# mcc.net
KiCad netlist of a schematic drawn in EAGLE
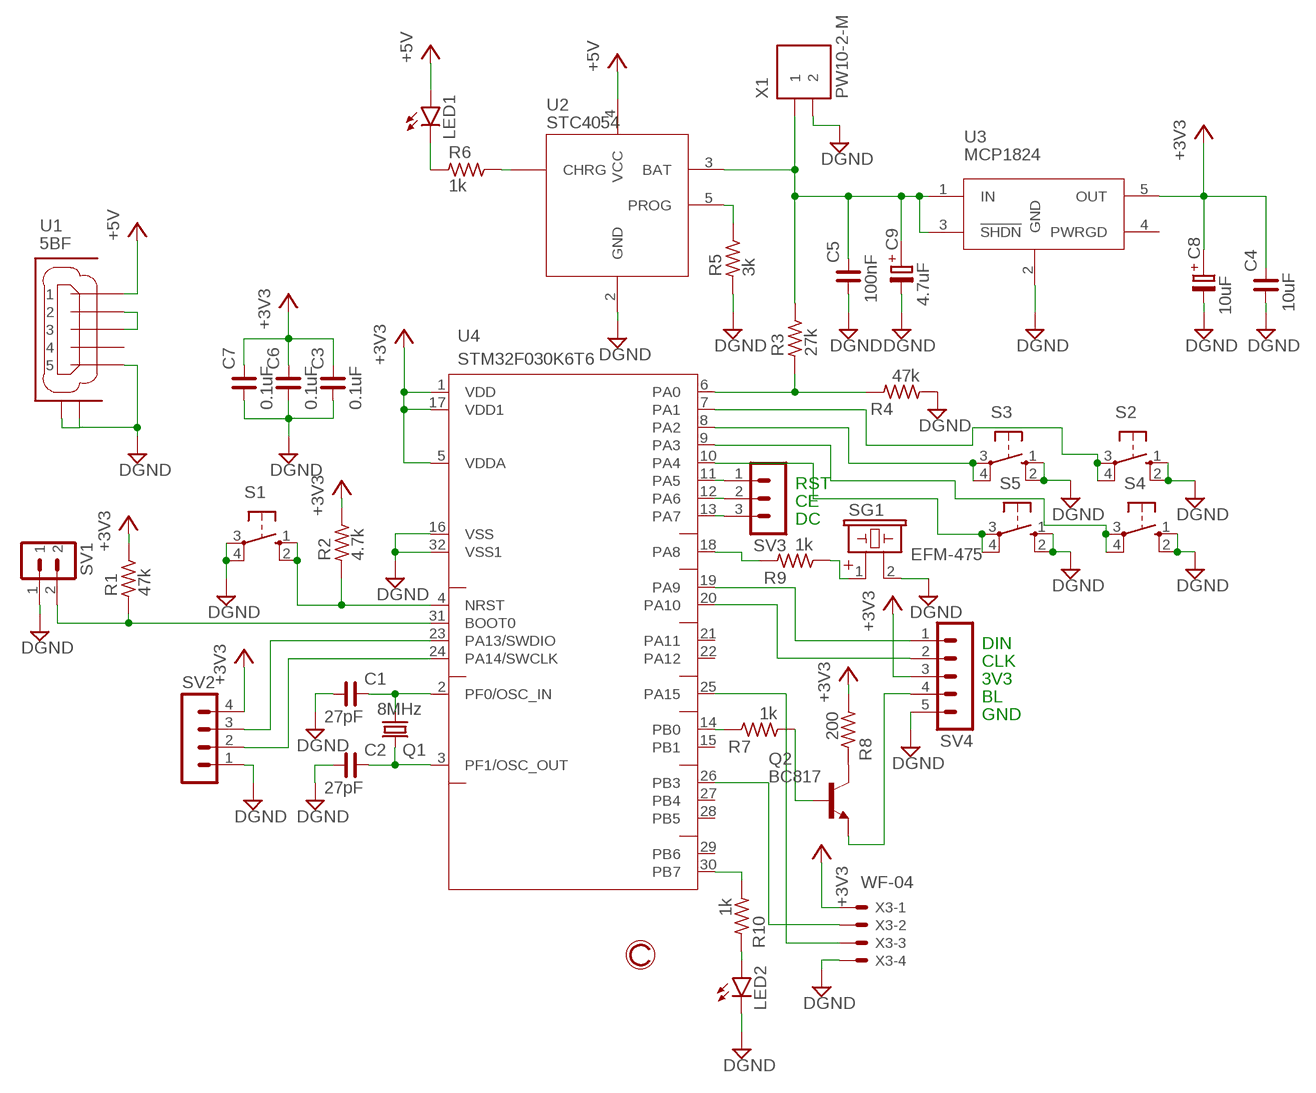
[diagram p0: schematic, sheet 1]

(export (version "E")
  (design (tool "Eeschema 10.0.6"))
  (components
    (comp (ref "C1")
      (value "27pF")
      (footprint "eagle-import:C0805")
      (libsource (lib "eagle-import") (part "C_0805"))
    )
    (comp (ref "C2")
      (value "27pF")
      (footprint "eagle-import:C0805")
      (libsource (lib "eagle-import") (part "C_0805"))
    )
    (comp (ref "C3")
      (value "0.1uF")
      (footprint "eagle-import:C0805")
      (libsource (lib "eagle-import") (part "C_0805"))
    )
    (comp (ref "C4")
      (value "10uF")
      (footprint "eagle-import:C1206")
      (libsource (lib "eagle-import") (part "C_1206"))
    )
    (comp (ref "C5")
      (value "100nF")
      (footprint "eagle-import:C0805")
      (libsource (lib "eagle-import") (part "C_0805"))
    )
    (comp (ref "C6")
      (value "0.1uF")
      (footprint "eagle-import:C0805")
      (libsource (lib "eagle-import") (part "C_0805"))
    )
    (comp (ref "C7")
      (value "0.1uF")
      (footprint "eagle-import:C0805")
      (libsource (lib "eagle-import") (part "C_0805"))
    )
    (comp (ref "C8")
      (value "10uF")
      (footprint "eagle-import:SV-C")
      (libsource (lib "eagle-import") (part "C-PR-SMD-SV-C"))
    )
    (comp (ref "C9")
      (value "4.7uF")
      (footprint "eagle-import:SV-C")
      (libsource (lib "eagle-import") (part "C-PR-SMD-SV-C"))
    )
    (comp (ref "LED1")
      (value "LEDSML0805")
      (footprint "eagle-import:SML0805")
      (libsource (lib "eagle-import") (part "LEDSML0805"))
    )
    (comp (ref "LED2")
      (value "LEDSML0805")
      (footprint "eagle-import:SML0805")
      (libsource (lib "eagle-import") (part "LEDSML0805"))
    )
    (comp (ref "Q1")
      (value "8MHz")
      (footprint "eagle-import:HC49UP")
      (libsource (lib "eagle-import") (part "CRYSTALHC49UP"))
    )
    (comp (ref "Q2")
      (value "BC817")
      (footprint "eagle-import:SOT23-BEC")
      (libsource (lib "eagle-import") (part "BC817SMD-40"))
    )
    (comp (ref "R1")
      (value "47k")
      (footprint "eagle-import:R0805")
      (libsource (lib "eagle-import") (part "R_0805"))
    )
    (comp (ref "R2")
      (value "4.7k")
      (footprint "eagle-import:R0805")
      (libsource (lib "eagle-import") (part "R_0805"))
    )
    (comp (ref "R3")
      (value "27k")
      (footprint "eagle-import:R0805")
      (libsource (lib "eagle-import") (part "R_0805"))
    )
    (comp (ref "R4")
      (value "47k")
      (footprint "eagle-import:R0805")
      (libsource (lib "eagle-import") (part "R_0805"))
    )
    (comp (ref "R5")
      (value "3k")
      (footprint "eagle-import:R0805")
      (libsource (lib "eagle-import") (part "R_0805"))
    )
    (comp (ref "R6")
      (value "1k")
      (footprint "eagle-import:R0805")
      (libsource (lib "eagle-import") (part "R_0805"))
    )
    (comp (ref "R7")
      (value "1k")
      (footprint "eagle-import:R0805")
      (libsource (lib "eagle-import") (part "R_0805"))
    )
    (comp (ref "R8")
      (value "200")
      (footprint "eagle-import:R0805")
      (libsource (lib "eagle-import") (part "R_0805"))
    )
    (comp (ref "R9")
      (value "1k")
      (footprint "eagle-import:R0805")
      (libsource (lib "eagle-import") (part "R_0805"))
    )
    (comp (ref "R10")
      (value "1k")
      (footprint "eagle-import:R0805")
      (libsource (lib "eagle-import") (part "R_0805"))
    )
    (comp (ref "S1")
      (value "10-XX")
      (footprint "eagle-import:B3F-10XX")
      (fields (field (name "MPN") "B3F-1000"))
      (libsource (lib "eagle-import") (part "10-XX"))
    )
    (comp (ref "S2")
      (value "10-XX")
      (footprint "eagle-import:B3F-10XX")
      (fields (field (name "MPN") "B3F-1000"))
      (libsource (lib "eagle-import") (part "10-XX"))
    )
    (comp (ref "S3")
      (value "10-XX")
      (footprint "eagle-import:B3F-10XX")
      (fields (field (name "MPN") "B3F-1000"))
      (libsource (lib "eagle-import") (part "10-XX"))
    )
    (comp (ref "S4")
      (value "10-XX")
      (footprint "eagle-import:B3F-10XX")
      (fields (field (name "MPN") "B3F-1000"))
      (libsource (lib "eagle-import") (part "10-XX"))
    )
    (comp (ref "S5")
      (value "10-XX")
      (footprint "eagle-import:B3F-10XX")
      (fields (field (name "MPN") "B3F-1000"))
      (libsource (lib "eagle-import") (part "10-XX"))
    )
    (comp (ref "SG1")
      (value "EFM-475")
      (footprint "eagle-import:EFM-472")
      (libsource (lib "eagle-import") (part "EFM-475"))
    )
    (comp (ref "SV1")
      (value "MA02-1")
      (footprint "eagle-import:MA02-1")
      (libsource (lib "eagle-import") (part "MA02-1"))
    )
    (comp (ref "SV2")
      (value "MA04-1")
      (footprint "eagle-import:MA04-1")
      (libsource (lib "eagle-import") (part "MA04-1"))
    )
    (comp (ref "SV3")
      (value "MA03-1")
      (footprint "eagle-import:MA03-1")
      (libsource (lib "eagle-import") (part "MA03-1"))
    )
    (comp (ref "SV4")
      (value "MA05-1")
      (footprint "eagle-import:MA05-1")
      (libsource (lib "eagle-import") (part "MA05-1"))
    )
    (comp (ref "U1")
      (value "5BF")
      (footprint "eagle-import:MICRO-USB-5BF")
      (libsource (lib "eagle-import") (part "MICRO-USB-5BF"))
    )
    (comp (ref "U2")
      (value "STC4054")
      (footprint "eagle-import:SOT23-5L")
      (libsource (lib "eagle-import") (part "STC4054"))
    )
    (comp (ref "U3")
      (value "MCP1824")
      (footprint "eagle-import:SOT23-5L")
      (libsource (lib "eagle-import") (part "MCP1824"))
    )
    (comp (ref "U4")
      (value "STM32F030K6T6")
      (footprint "eagle-import:LQFP-32")
      (libsource (lib "eagle-import") (part "STM32F030K6T6"))
    )
    (comp (ref "X1")
      (value "PW10-2-M")
      (footprint "eagle-import:MKS1852-6-0-202")
      (libsource (lib "eagle-import") (part "MKS1852-6-0-202"))
    )
    (comp (ref "X3")
      (value "WF-04")
      (footprint "eagle-import:22-23-2041")
      (fields (field (name "MF") "MOLEX") (field (name "MPN") "22-23-2041"))
      (libsource (lib "eagle-import") (part "22-23-2041"))
    )
  )
  (nets
    (net (code "1") (name "+3V3") (class "Default")
      (node (ref "C3") (pin "2") (pinfunction "2_2") (pintype "passive"))
      (node (ref "C4") (pin "2") (pinfunction "2_2") (pintype "passive"))
      (node (ref "C6") (pin "2") (pinfunction "2_2") (pintype "passive"))
      (node (ref "C7") (pin "2") (pinfunction "2_2") (pintype "passive"))
      (node (ref "C8") (pin "+") (pinfunction "+_+") (pintype "passive"))
      (node (ref "R1") (pin "2") (pinfunction "2_2") (pintype "passive"))
      (node (ref "R2") (pin "2") (pinfunction "2_2") (pintype "passive"))
      (node (ref "R8") (pin "1") (pinfunction "1_1") (pintype "passive"))
      (node (ref "SV2") (pin "4") (pinfunction "4_4") (pintype "passive"))
      (node (ref "SV4") (pin "3") (pinfunction "3_3") (pintype "passive"))
      (node (ref "U3") (pin "5") (pinfunction "OUT_5") (pintype "bidirectional"))
      (node (ref "U4") (pin "1") (pinfunction "VDD_1") (pintype "bidirectional"))
      (node (ref "U4") (pin "17") (pinfunction "VDD1_17") (pintype "bidirectional"))
      (node (ref "U4") (pin "5") (pinfunction "VDDA_5") (pintype "bidirectional"))
      (node (ref "X3") (pin "1") (pinfunction "S_1") (pintype "passive"))
    )
    (net (code "2") (name "+5V") (class "Default")
      (node (ref "LED1") (pin "A") (pinfunction "A_A") (pintype "passive"))
      (node (ref "U1") (pin "1") (pinfunction "1_1") (pintype "input"))
      (node (ref "U2") (pin "4") (pinfunction "VCC_4") (pintype "bidirectional"))
    )
    (net (code "3") (name "DGND") (class "Default")
      (node (ref "C1") (pin "1") (pinfunction "1_1") (pintype "passive"))
      (node (ref "C2") (pin "1") (pinfunction "1_1") (pintype "passive"))
      (node (ref "C3") (pin "1") (pinfunction "1_1") (pintype "passive"))
      (node (ref "C4") (pin "1") (pinfunction "1_1") (pintype "passive"))
      (node (ref "C5") (pin "1") (pinfunction "1_1") (pintype "passive"))
      (node (ref "C6") (pin "1") (pinfunction "1_1") (pintype "passive"))
      (node (ref "C7") (pin "1") (pinfunction "1_1") (pintype "passive"))
      (node (ref "C8") (pin "-") (pinfunction "-_-") (pintype "passive"))
      (node (ref "C9") (pin "-") (pinfunction "-_-") (pintype "passive"))
      (node (ref "LED2") (pin "C") (pinfunction "C_C") (pintype "passive"))
      (node (ref "R4") (pin "1") (pinfunction "1_1") (pintype "passive"))
      (node (ref "R5") (pin "1") (pinfunction "1_1") (pintype "passive"))
      (node (ref "S1") (pin "3") (pinfunction "P_3") (pintype "passive"))
      (node (ref "S1") (pin "4") (pinfunction "P1_4") (pintype "passive"))
      (node (ref "S2") (pin "1") (pinfunction "S_1") (pintype "passive"))
      (node (ref "S2") (pin "2") (pinfunction "S1_2") (pintype "passive"))
      (node (ref "S3") (pin "1") (pinfunction "S_1") (pintype "passive"))
      (node (ref "S3") (pin "2") (pinfunction "S1_2") (pintype "passive"))
      (node (ref "S4") (pin "1") (pinfunction "S_1") (pintype "passive"))
      (node (ref "S4") (pin "2") (pinfunction "S1_2") (pintype "passive"))
      (node (ref "S5") (pin "1") (pinfunction "S_1") (pintype "passive"))
      (node (ref "S5") (pin "2") (pinfunction "S1_2") (pintype "passive"))
      (node (ref "SG1") (pin "2") (pinfunction "2_2") (pintype "passive"))
      (node (ref "SV1") (pin "1") (pinfunction "1_1") (pintype "passive"))
      (node (ref "SV2") (pin "1") (pinfunction "1_1") (pintype "passive"))
      (node (ref "SV4") (pin "5") (pinfunction "5_5") (pintype "passive"))
      (node (ref "U1") (pin "5") (pinfunction "5_5") (pintype "input"))
      (node (ref "U1") (pin "GND1") (pinfunction "GND1_GND1") (pintype "bidirectional"))
      (node (ref "U1") (pin "GND2") (pinfunction "GND2_GND2") (pintype "bidirectional"))
      (node (ref "U2") (pin "2") (pinfunction "GND_2") (pintype "bidirectional"))
      (node (ref "U3") (pin "2") (pinfunction "GND_2") (pintype "bidirectional"))
      (node (ref "U4") (pin "16") (pinfunction "VSS_16") (pintype "bidirectional"))
      (node (ref "U4") (pin "32") (pinfunction "VSS1_32") (pintype "bidirectional"))
      (node (ref "X1") (pin "2") (pinfunction "2_2") (pintype "input"))
      (node (ref "X3") (pin "4") (pinfunction "S_4") (pintype "passive"))
    )
    (net (code "4") (name "Net-(LED1-PadC)") (class "Default")
      (node (ref "LED1") (pin "C") (pinfunction "C_C") (pintype "passive"))
      (node (ref "R6") (pin "1") (pinfunction "1_1") (pintype "passive"))
    )
    (net (code "5") (name "Net-(LED2-PadA)") (class "Default")
      (node (ref "LED2") (pin "A") (pinfunction "A_A") (pintype "passive"))
      (node (ref "R10") (pin "2") (pinfunction "2_2") (pintype "passive"))
    )
    (net (code "6") (name "Net-(Q2-PadB)") (class "Default")
      (node (ref "Q2") (pin "B") (pinfunction "B_B") (pintype "passive"))
      (node (ref "R7") (pin "1") (pinfunction "1_1") (pintype "passive"))
    )
    (net (code "7") (name "Net-(Q2-PadC)") (class "Default")
      (node (ref "Q2") (pin "C") (pinfunction "C_C") (pintype "passive"))
      (node (ref "R8") (pin "2") (pinfunction "2_2") (pintype "passive"))
    )
    (net (code "8") (name "Net-(Q2-PadE)") (class "Default")
      (node (ref "Q2") (pin "E") (pinfunction "E_E") (pintype "passive"))
      (node (ref "SV4") (pin "4") (pinfunction "4_4") (pintype "passive"))
    )
    (net (code "9") (name "Net-(R9-Pad1)") (class "Default")
      (node (ref "R9") (pin "1") (pinfunction "1_1") (pintype "passive"))
      (node (ref "SG1") (pin "1") (pinfunction "1_1") (pintype "passive"))
    )
    (net (code "10") (name "Net-(S1-S)") (class "Default")
      (node (ref "R2") (pin "1") (pinfunction "1_1") (pintype "passive"))
      (node (ref "S1") (pin "1") (pinfunction "S_1") (pintype "passive"))
      (node (ref "S1") (pin "2") (pinfunction "S1_2") (pintype "passive"))
      (node (ref "U4") (pin "4") (pinfunction "NRST_4") (pintype "bidirectional"))
    )
    (net (code "11") (name "Net-(S2-P)") (class "Default")
      (node (ref "S2") (pin "3") (pinfunction "P_3") (pintype "passive"))
      (node (ref "S2") (pin "4") (pinfunction "P1_4") (pintype "passive"))
      (node (ref "U4") (pin "7") (pinfunction "PA1_7") (pintype "bidirectional"))
    )
    (net (code "12") (name "Net-(S3-P)") (class "Default")
      (node (ref "S3") (pin "3") (pinfunction "P_3") (pintype "passive"))
      (node (ref "S3") (pin "4") (pinfunction "P1_4") (pintype "passive"))
      (node (ref "U4") (pin "8") (pinfunction "PA2_8") (pintype "bidirectional"))
    )
    (net (code "13") (name "Net-(S4-P)") (class "Default")
      (node (ref "S4") (pin "3") (pinfunction "P_3") (pintype "passive"))
      (node (ref "S4") (pin "4") (pinfunction "P1_4") (pintype "passive"))
      (node (ref "U4") (pin "9") (pinfunction "PA3_9") (pintype "bidirectional"))
    )
    (net (code "14") (name "Net-(S5-P)") (class "Default")
      (node (ref "S5") (pin "3") (pinfunction "P_3") (pintype "passive"))
      (node (ref "S5") (pin "4") (pinfunction "P1_4") (pintype "passive"))
      (node (ref "U4") (pin "10") (pinfunction "PA4_10") (pintype "bidirectional"))
    )
    (net (code "15") (name "Net-(U1-Pad2)") (class "Default")
      (node (ref "U1") (pin "2") (pinfunction "2_2") (pintype "input"))
      (node (ref "U1") (pin "3") (pinfunction "3_3") (pintype "input"))
    )
    (net (code "16") (name "Net-(U2-BAT)") (class "Default")
      (node (ref "C5") (pin "2") (pinfunction "2_2") (pintype "passive"))
      (node (ref "C9") (pin "+") (pinfunction "+_+") (pintype "passive"))
      (node (ref "R3") (pin "2") (pinfunction "2_2") (pintype "passive"))
      (node (ref "U2") (pin "3") (pinfunction "BAT_3") (pintype "bidirectional"))
      (node (ref "U3") (pin "1") (pinfunction "IN_1") (pintype "bidirectional"))
      (node (ref "U3") (pin "3") (pinfunction "~{SHDN}_3") (pintype "bidirectional"))
      (node (ref "X1") (pin "1") (pinfunction "1_1") (pintype "input"))
    )
    (net (code "17") (name "Net-(U2-CHRG)") (class "Default")
      (node (ref "R6") (pin "2") (pinfunction "2_2") (pintype "passive"))
      (node (ref "U2") (pin "1") (pinfunction "CHRG_1") (pintype "bidirectional"))
    )
    (net (code "18") (name "Net-(U2-PROG)") (class "Default")
      (node (ref "R5") (pin "2") (pinfunction "2_2") (pintype "passive"))
      (node (ref "U2") (pin "5") (pinfunction "PROG_5") (pintype "bidirectional"))
    )
    (net (code "19") (name "Net-(U4-BOOT0)") (class "Default")
      (node (ref "R1") (pin "1") (pinfunction "1_1") (pintype "passive"))
      (node (ref "SV1") (pin "2") (pinfunction "2_2") (pintype "passive"))
      (node (ref "U4") (pin "31") (pinfunction "BOOT0_31") (pintype "bidirectional"))
    )
    (net (code "20") (name "Net-(U4-PA0)") (class "Default")
      (node (ref "R3") (pin "1") (pinfunction "1_1") (pintype "passive"))
      (node (ref "R4") (pin "2") (pinfunction "2_2") (pintype "passive"))
      (node (ref "U4") (pin "6") (pinfunction "PA0_6") (pintype "bidirectional"))
    )
    (net (code "21") (name "Net-(U4-PA5)") (class "Default")
      (node (ref "SV3") (pin "1") (pinfunction "1_1") (pintype "passive"))
      (node (ref "U4") (pin "11") (pinfunction "PA5_11") (pintype "bidirectional"))
    )
    (net (code "22") (name "Net-(U4-PA6)") (class "Default")
      (node (ref "SV3") (pin "2") (pinfunction "2_2") (pintype "passive"))
      (node (ref "U4") (pin "12") (pinfunction "PA6_12") (pintype "bidirectional"))
    )
    (net (code "23") (name "Net-(U4-PA7)") (class "Default")
      (node (ref "SV3") (pin "3") (pinfunction "3_3") (pintype "passive"))
      (node (ref "U4") (pin "13") (pinfunction "PA7_13") (pintype "bidirectional"))
    )
    (net (code "24") (name "Net-(U4-PA8)") (class "Default")
      (node (ref "R9") (pin "2") (pinfunction "2_2") (pintype "passive"))
      (node (ref "U4") (pin "18") (pinfunction "PA8_18") (pintype "bidirectional"))
    )
    (net (code "25") (name "Net-(U4-PA9)") (class "Default")
      (node (ref "SV4") (pin "1") (pinfunction "1_1") (pintype "passive"))
      (node (ref "U4") (pin "19") (pinfunction "PA9_19") (pintype "bidirectional"))
    )
    (net (code "26") (name "Net-(U4-PA10)") (class "Default")
      (node (ref "SV4") (pin "2") (pinfunction "2_2") (pintype "passive"))
      (node (ref "U4") (pin "20") (pinfunction "PA10_20") (pintype "bidirectional"))
    )
    (net (code "27") (name "Net-(U4-PA13{slash}SWDIO)") (class "Default")
      (node (ref "SV2") (pin "3") (pinfunction "3_3") (pintype "passive"))
      (node (ref "U4") (pin "23") (pinfunction "PA13/SWDIO_23") (pintype "bidirectional"))
    )
    (net (code "28") (name "Net-(U4-PA14{slash}SWCLK)") (class "Default")
      (node (ref "SV2") (pin "2") (pinfunction "2_2") (pintype "passive"))
      (node (ref "U4") (pin "24") (pinfunction "PA14/SWCLK_24") (pintype "bidirectional"))
    )
    (net (code "29") (name "Net-(U4-PA15)") (class "Default")
      (node (ref "U4") (pin "25") (pinfunction "PA15_25") (pintype "bidirectional"))
      (node (ref "X3") (pin "3") (pinfunction "S_3") (pintype "passive"))
    )
    (net (code "30") (name "Net-(U4-PB0)") (class "Default")
      (node (ref "R7") (pin "2") (pinfunction "2_2") (pintype "passive"))
      (node (ref "U4") (pin "14") (pinfunction "PB0_14") (pintype "bidirectional"))
    )
    (net (code "31") (name "Net-(U4-PB3)") (class "Default")
      (node (ref "U4") (pin "26") (pinfunction "PB3_26") (pintype "bidirectional"))
      (node (ref "X3") (pin "2") (pinfunction "S_2") (pintype "passive"))
    )
    (net (code "32") (name "Net-(U4-PB7)") (class "Default")
      (node (ref "R10") (pin "1") (pinfunction "1_1") (pintype "passive"))
      (node (ref "U4") (pin "30") (pinfunction "PB7_30") (pintype "bidirectional"))
    )
    (net (code "33") (name "Net-(U4-PF0{slash}OSC_IN)") (class "Default")
      (node (ref "C1") (pin "2") (pinfunction "2_2") (pintype "passive"))
      (node (ref "Q1") (pin "1") (pinfunction "1_1") (pintype "passive"))
      (node (ref "U4") (pin "2") (pinfunction "PF0/OSC_IN_2") (pintype "bidirectional"))
    )
    (net (code "34") (name "Net-(U4-PF1{slash}OSC_OUT)") (class "Default")
      (node (ref "C2") (pin "2") (pinfunction "2_2") (pintype "passive"))
      (node (ref "Q1") (pin "2") (pinfunction "2_2") (pintype "passive"))
      (node (ref "U4") (pin "3") (pinfunction "PF1/OSC_OUT_3") (pintype "bidirectional"))
    )
    (net (code "35") (name "unconnected-(U1-Pad4)") (class "Default")
      (node (ref "U1") (pin "4") (pinfunction "4_4") (pintype "input"))
    )
    (net (code "36") (name "unconnected-(U3-PWRGD-Pad4)") (class "Default")
      (node (ref "U3") (pin "4") (pinfunction "PWRGD_4") (pintype "bidirectional"))
    )
    (net (code "37") (name "unconnected-(U4-PA11-Pad21)") (class "Default")
      (node (ref "U4") (pin "21") (pinfunction "PA11_21") (pintype "bidirectional"))
    )
    (net (code "38") (name "unconnected-(U4-PA12-Pad22)") (class "Default")
      (node (ref "U4") (pin "22") (pinfunction "PA12_22") (pintype "bidirectional"))
    )
    (net (code "39") (name "unconnected-(U4-PB1-Pad15)") (class "Default")
      (node (ref "U4") (pin "15") (pinfunction "PB1_15") (pintype "bidirectional"))
    )
    (net (code "40") (name "unconnected-(U4-PB4-Pad27)") (class "Default")
      (node (ref "U4") (pin "27") (pinfunction "PB4_27") (pintype "bidirectional"))
    )
    (net (code "41") (name "unconnected-(U4-PB5-Pad28)") (class "Default")
      (node (ref "U4") (pin "28") (pinfunction "PB5_28") (pintype "bidirectional"))
    )
    (net (code "42") (name "unconnected-(U4-PB6-Pad29)") (class "Default")
      (node (ref "U4") (pin "29") (pinfunction "PB6_29") (pintype "bidirectional"))
    )
  )
)
